# SCH_Display_LPM027M128B_breakout_2021-11.net
KiCad netlist of a schematic drawn in EasyEDA
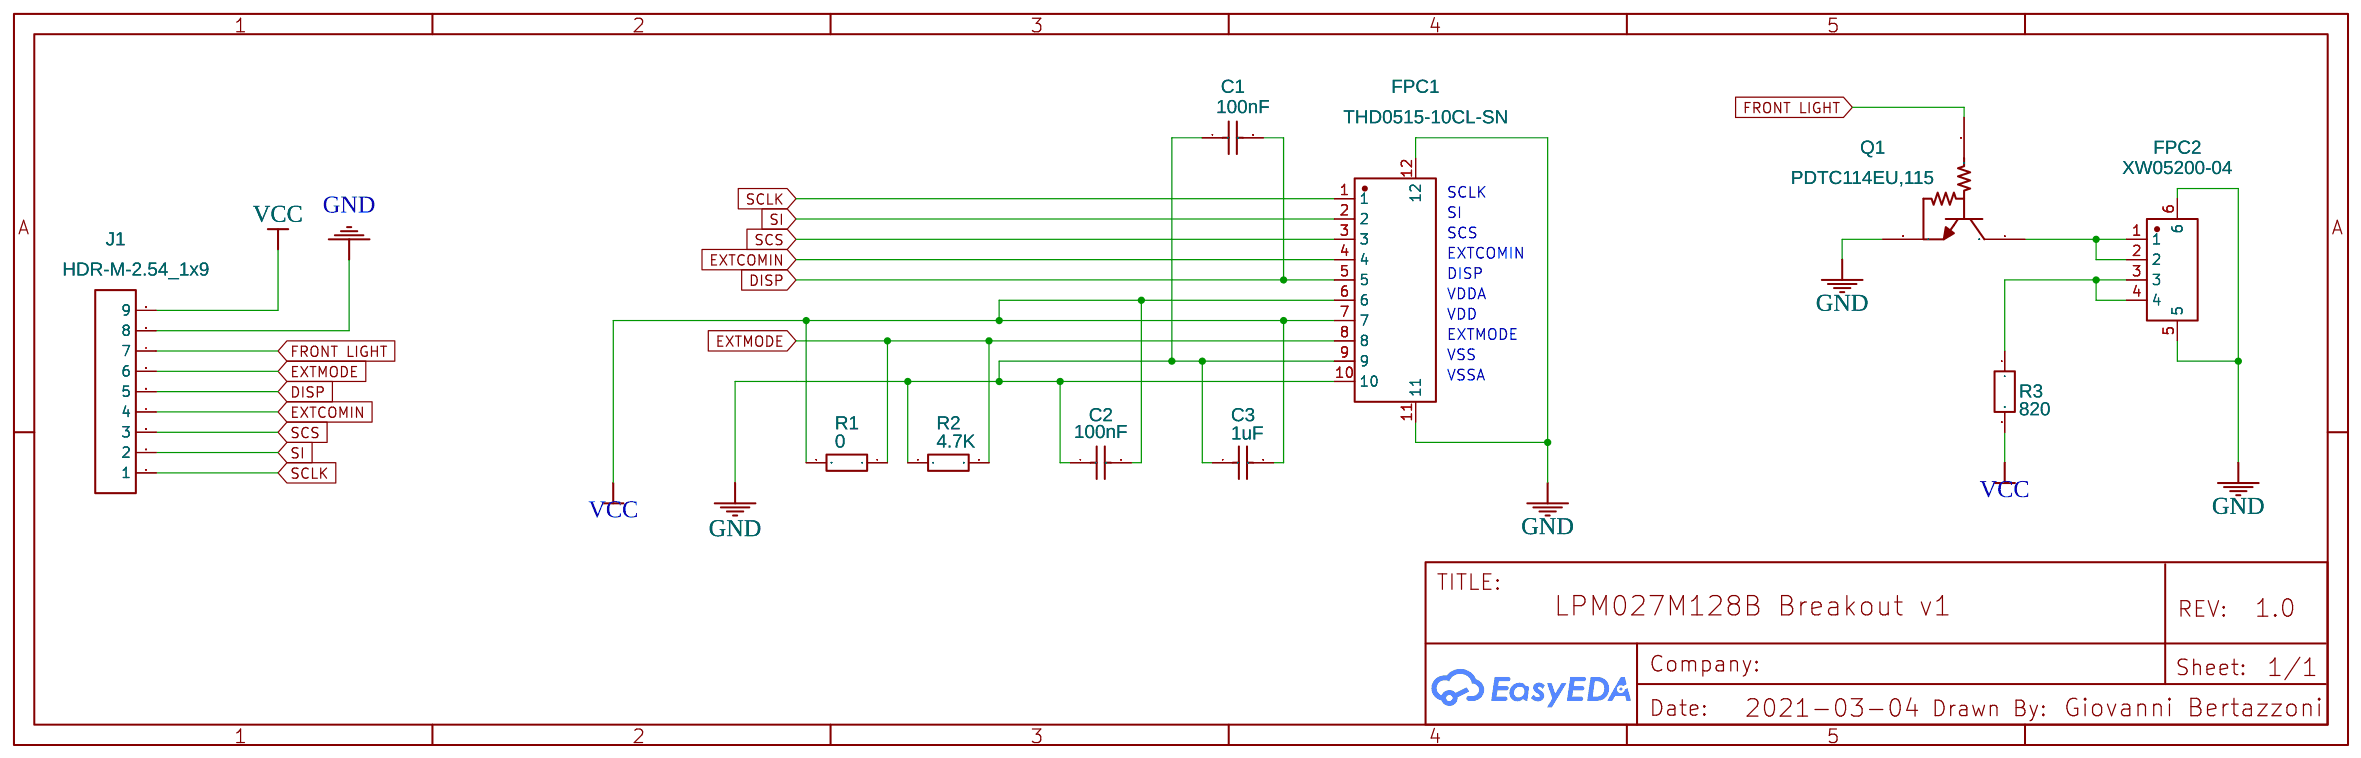
[diagram p0: schematic sheet]

(export (version "E")
  (design (tool "Eeschema 10.0.6"))
  (components
    (comp (ref "C1")
      (value "100nF")
      (fields
        (field (name "BOM_Manufacturer Part") "0603B104K160")
        (field (name "BOM_Supplier Part") "C80516")
      )
      (libsource (lib "") (part "0603B104K160"))
    )
    (comp (ref "C2")
      (value "100nF")
      (fields
        (field (name "BOM_Manufacturer Part") "0603B104K160")
        (field (name "BOM_Supplier Part") "C80516")
      )
      (libsource (lib "") (part "0603B104K160"))
    )
    (comp (ref "C3")
      (value "1uF")
      (fields
        (field (name "BOM_Manufacturer Part") "CC0805KKX7R7BB105")
        (field (name "BOM_Supplier Part") "C94122")
      )
      (libsource (lib "") (part "CC0805KKX7R7BB105"))
    )
    (comp (ref "FPC1")
      (value "THD0515-10CL-SN")
      (fields (field (name "BOM_Supplier Part") "C283142"))
      (libsource (lib "") (part "THD0515-10CL-SN"))
    )
    (comp (ref "FPC2")
      (value "XW05200-04")
      (fields (field (name "BOM_Supplier Part") "C376056"))
      (libsource (lib "") (part "XW05200-04"))
    )
    (comp (ref "J1")
      (value "HDR-M-2.54_1x9")
      (fields (field (name "BOM_Supplier Part") "C225484"))
      (libsource (lib "") (part "HDR-M-2.54_1x9"))
    )
    (comp (ref "Q1")
      (value "PDTC114EU,115")
      (fields (field (name "BOM_Supplier Part") "C135830"))
      (libsource (lib "") (part "PDTC114EU,115"))
    )
    (comp (ref "R1")
      (value "0")
      (fields
        (field (name "BOM_Manufacturer Part") "WR12X0000FTL")
        (field (name "BOM_Supplier Part") "C164015")
      )
      (libsource (lib "") (part "WR12X0000FTL"))
    )
    (comp (ref "R2")
      (value "4.7K")
      (fields
        (field (name "BOM_Manufacturer Part") "WR06X472JTL")
        (field (name "BOM_Supplier Part") "C163915")
      )
      (libsource (lib "") (part "WR06X472JTL_C163915"))
    )
    (comp (ref "R3")
      (value "820")
      (fields
        (field (name "BOM_Manufacturer Part") "AS05W2J0821T5E")
        (field (name "BOM_Supplier Part") "C966098")
      )
      (libsource (lib "") (part "AS05W2J0821T5E"))
    )
  )
  (nets
    (net (code "1") (name "DISP") (class "Default")
      (node (ref "C1") (pin "2") (pinfunction "2_2") (pintype "input"))
      (node (ref "FPC1") (pin "5") (pinfunction "5_5") (pintype "unspecified"))
      (node (ref "J1") (pin "5") (pinfunction "5_5") (pintype "unspecified"))
    )
    (net (code "2") (name "EXTCOMIN") (class "Default")
      (node (ref "FPC1") (pin "4") (pinfunction "4_4") (pintype "unspecified"))
      (node (ref "J1") (pin "4") (pinfunction "4_4") (pintype "unspecified"))
    )
    (net (code "3") (name "EXTMODE") (class "Default")
      (node (ref "FPC1") (pin "8") (pinfunction "8_8") (pintype "unspecified"))
      (node (ref "J1") (pin "6") (pinfunction "6_6") (pintype "unspecified"))
      (node (ref "R1") (pin "1") (pinfunction "1_1") (pintype "unspecified"))
      (node (ref "R2") (pin "2") (pinfunction "2_2") (pintype "unspecified"))
    )
    (net (code "4") (name "FRONT LIGHT") (class "Default")
      (node (ref "J1") (pin "7") (pinfunction "7_7") (pintype "unspecified"))
      (node (ref "Q1") (pin "1") (pinfunction "B_1") (pintype "unspecified"))
    )
    (net (code "5") (name "GND") (class "Default")
      (node (ref "C1") (pin "1") (pinfunction "1_1") (pintype "input"))
      (node (ref "C2") (pin "1") (pinfunction "1_1") (pintype "input"))
      (node (ref "C3") (pin "1") (pinfunction "1_1") (pintype "input"))
      (node (ref "FPC1") (pin "10") (pinfunction "10_10") (pintype "unspecified"))
      (node (ref "FPC1") (pin "11") (pinfunction "11_11") (pintype "unspecified"))
      (node (ref "FPC1") (pin "12") (pinfunction "12_12") (pintype "unspecified"))
      (node (ref "FPC1") (pin "9") (pinfunction "9_9") (pintype "unspecified"))
      (node (ref "FPC2") (pin "5") (pinfunction "5_5") (pintype "unspecified"))
      (node (ref "FPC2") (pin "6") (pinfunction "6_6") (pintype "unspecified"))
      (node (ref "J1") (pin "8") (pinfunction "8_8") (pintype "unspecified"))
      (node (ref "Q1") (pin "2") (pinfunction "E_2") (pintype "unspecified"))
      (node (ref "R2") (pin "1") (pinfunction "1_1") (pintype "unspecified"))
    )
    (net (code "6") (name "Net-(FPC2-Pad3)") (class "Default")
      (node (ref "FPC2") (pin "3") (pinfunction "3_3") (pintype "unspecified"))
      (node (ref "FPC2") (pin "4") (pinfunction "4_4") (pintype "unspecified"))
      (node (ref "R3") (pin "1") (pinfunction "1_1") (pintype "unspecified"))
    )
    (net (code "7") (name "Net-(Q1-C)") (class "Default")
      (node (ref "FPC2") (pin "1") (pinfunction "1_1") (pintype "unspecified"))
      (node (ref "FPC2") (pin "2") (pinfunction "2_2") (pintype "unspecified"))
      (node (ref "Q1") (pin "3") (pinfunction "C_3") (pintype "unspecified"))
    )
    (net (code "8") (name "SCLK") (class "Default")
      (node (ref "FPC1") (pin "1") (pinfunction "1_1") (pintype "unspecified"))
      (node (ref "J1") (pin "1") (pinfunction "1_1") (pintype "unspecified"))
    )
    (net (code "9") (name "SCS") (class "Default")
      (node (ref "FPC1") (pin "3") (pinfunction "3_3") (pintype "unspecified"))
      (node (ref "J1") (pin "3") (pinfunction "3_3") (pintype "unspecified"))
    )
    (net (code "10") (name "SI") (class "Default")
      (node (ref "FPC1") (pin "2") (pinfunction "2_2") (pintype "unspecified"))
      (node (ref "J1") (pin "2") (pinfunction "2_2") (pintype "unspecified"))
    )
    (net (code "11") (name "VCC") (class "Default")
      (node (ref "C2") (pin "2") (pinfunction "2_2") (pintype "input"))
      (node (ref "C3") (pin "2") (pinfunction "2_2") (pintype "input"))
      (node (ref "FPC1") (pin "6") (pinfunction "6_6") (pintype "unspecified"))
      (node (ref "FPC1") (pin "7") (pinfunction "7_7") (pintype "unspecified"))
      (node (ref "J1") (pin "9") (pinfunction "9_9") (pintype "unspecified"))
      (node (ref "R1") (pin "2") (pinfunction "2_2") (pintype "unspecified"))
      (node (ref "R3") (pin "2") (pinfunction "2_2") (pintype "unspecified"))
    )
  )
)
